# LaserCutterControlSimple.net
KiCad netlist of a schematic drawn in EAGLE
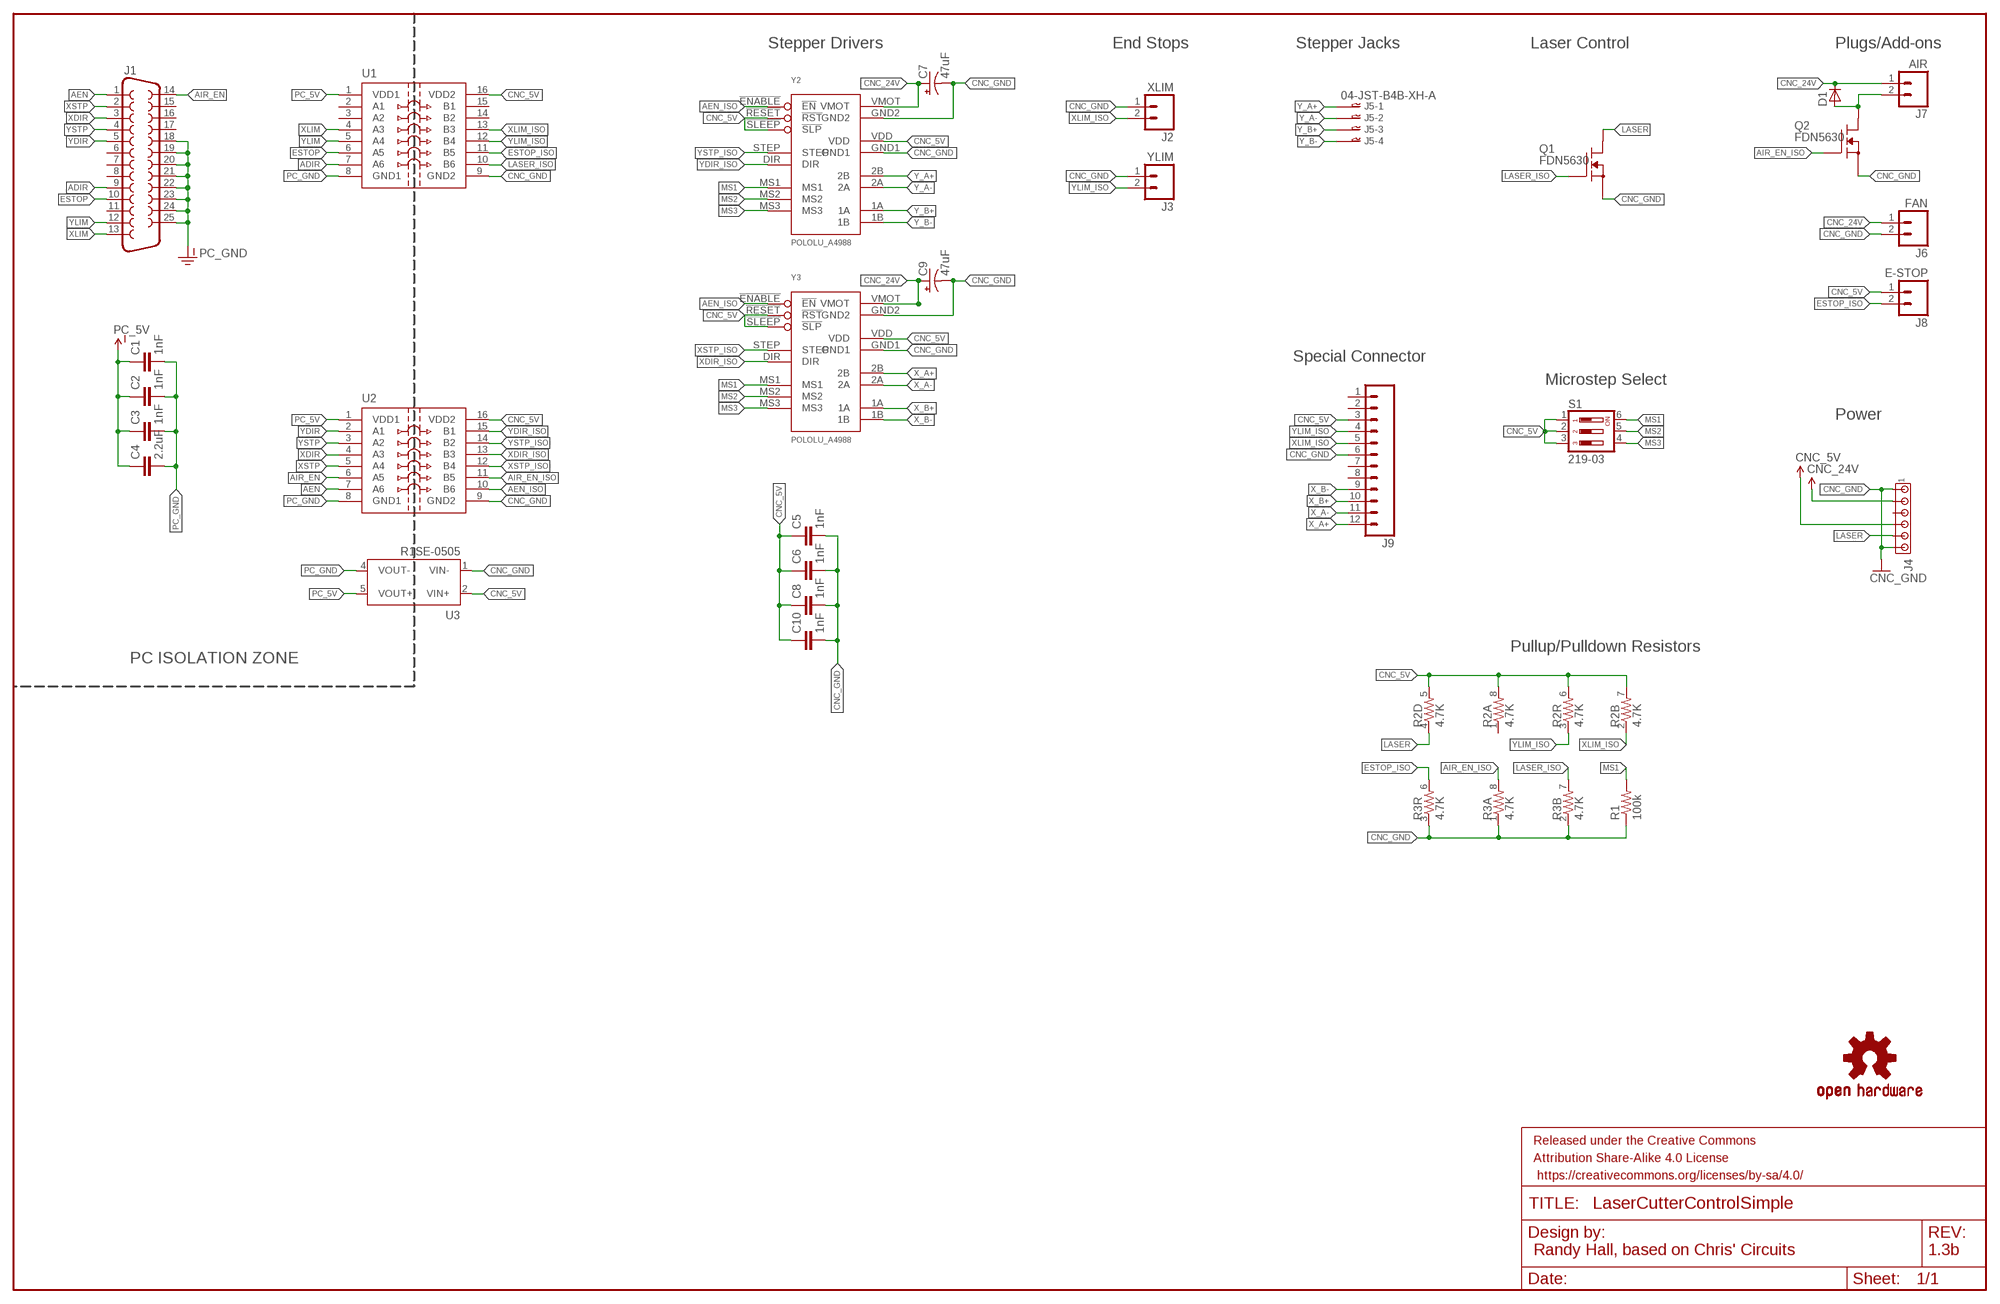
[diagram p0: schematic, sheet 1]

(export (version "E")
  (design (tool "Eeschema 10.0.6"))
  (components
    (comp (ref "C1")
      (value "1nF")
      (footprint "eagle-import:0603-CAP")
      (libsource (lib "eagle-import") (part "1NF/1000PF-50V-10%(0603)"))
    )
    (comp (ref "C2")
      (value "1nF")
      (footprint "eagle-import:0603-CAP")
      (libsource (lib "eagle-import") (part "1NF/1000PF-50V-10%(0603)"))
    )
    (comp (ref "C3")
      (value "1nF")
      (footprint "eagle-import:0603-CAP")
      (libsource (lib "eagle-import") (part "1NF/1000PF-50V-10%(0603)"))
    )
    (comp (ref "C4")
      (value "2.2uF")
      (footprint "eagle-import:0603-CAP")
      (libsource (lib "eagle-import") (part "1NF/1000PF-50V-10%(0603)"))
    )
    (comp (ref "C5")
      (value "1nF")
      (footprint "eagle-import:0603-CAP")
      (libsource (lib "eagle-import") (part "1NF/1000PF-50V-10%(0603)"))
    )
    (comp (ref "C6")
      (value "1nF")
      (footprint "eagle-import:0603-CAP")
      (libsource (lib "eagle-import") (part "1NF/1000PF-50V-10%(0603)"))
    )
    (comp (ref "C7")
      (value "47uF")
      (footprint "eagle-import:PANASONIC_E")
      (libsource (lib "eagle-import") (part "CPOL-USE"))
    )
    (comp (ref "C8")
      (value "1nF")
      (footprint "eagle-import:0603-CAP")
      (libsource (lib "eagle-import") (part "1NF/1000PF-50V-10%(0603)"))
    )
    (comp (ref "C9")
      (value "47uF")
      (footprint "eagle-import:PANASONIC_E")
      (libsource (lib "eagle-import") (part "CPOL-USE"))
    )
    (comp (ref "C10")
      (value "1nF")
      (footprint "eagle-import:0603-CAP")
      (libsource (lib "eagle-import") (part "1NF/1000PF-50V-10%(0603)"))
    )
    (comp (ref "D1")
      (value "D-SOD123")
      (footprint "eagle-import:SOD123")
      (libsource (lib "eagle-import") (part "D-SOD123"))
    )
    (comp (ref "FRAME1")
      (value "FRAME-LEDGER")
      (footprint "eagle-import:CREATIVE_COMMONS")
      (libsource (lib "eagle-import") (part "FRAME-LEDGER"))
    )
    (comp (ref "J1")
      (value "F25HP")
      (footprint "eagle-import:F25HP")
      (libsource (lib "eagle-import") (part "F25HP"))
    )
    (comp (ref "J2")
      (value "XLIM")
      (footprint "eagle-import:1X02")
      (libsource (lib "eagle-import") (part "M02PTH"))
    )
    (comp (ref "J3")
      (value "YLIM")
      (footprint "eagle-import:1X02")
      (libsource (lib "eagle-import") (part "M02PTH"))
    )
    (comp (ref "J4")
      (value "MTA06-156")
      (footprint "eagle-import:1X6MTA")
      (libsource (lib "eagle-import") (part "MTA06-156"))
    )
    (comp (ref "J5")
      (value "04-JST-B4B-XH-A")
      (footprint "eagle-import:B4B-XH")
      (libsource (lib "eagle-import") (part "04-JST-B4B-XH-A"))
    )
    (comp (ref "J6")
      (value "FAN")
      (footprint "eagle-import:1X02")
      (libsource (lib "eagle-import") (part "M02PTH"))
    )
    (comp (ref "J7")
      (value "AIR")
      (footprint "eagle-import:1X02")
      (libsource (lib "eagle-import") (part "M02PTH"))
    )
    (comp (ref "J8")
      (value "E-STOP")
      (footprint "eagle-import:1X02")
      (libsource (lib "eagle-import") (part "M02PTH"))
    )
    (comp (ref "J9")
      (value "M12")
      (footprint "eagle-import:12P")
      (libsource (lib "eagle-import") (part "M12"))
    )
    (comp (ref "LOGO1")
      (value "OSHW-LOGOM")
      (footprint "eagle-import:OSHW-LOGO-M")
      (libsource (lib "eagle-import") (part "OSHW-LOGOM"))
    )
    (comp (ref "Q1")
      (value "FDN5630")
      (footprint "eagle-import:SOT23")
      (libsource (lib "eagle-import") (part "FDN5630"))
    )
    (comp (ref "Q2")
      (value "FDN5630")
      (footprint "eagle-import:SOT23")
      (libsource (lib "eagle-import") (part "FDN5630"))
    )
    (comp (ref "R1")
      (value "100k")
      (footprint "eagle-import:0603-RES")
      (libsource (lib "eagle-import") (part "100KOHM1/10W1%(0603)"))
    )
    (comp (ref "R2")
      (value "4.7K")
      (footprint "eagle-import:0603-ARV")
      (libsource (lib "eagle-import") (part "RESISTOR-ARRAY0603-ARV"))
    )
    (comp (ref "R3")
      (value "4.7K")
      (footprint "eagle-import:0603-ARV")
      (libsource (lib "eagle-import") (part "RESISTOR-ARRAY0603-ARV"))
    )
    (comp (ref "S1")
      (value "219-03")
      (footprint "eagle-import:CTS-219-03")
      (libsource (lib "eagle-import") (part "219-03"))
    )
    (comp (ref "U1")
      (value "SI8460IS1")
      (footprint "eagle-import:SO16")
      (libsource (lib "eagle-import") (part "SI8460IS1"))
    )
    (comp (ref "U2")
      (value "SI8460IS1")
      (footprint "eagle-import:SO16")
      (libsource (lib "eagle-import") (part "SI8460IS1"))
    )
    (comp (ref "U3")
      (value "R1SE-0505")
      (footprint "eagle-import:SMD5")
      (libsource (lib "eagle-import") (part "R1SE-0505"))
    )
    (comp (ref "Y2")
      (value "POLOLU_A4988")
      (footprint "eagle-import:POLOLU_STEPPER_DRIVER")
      (libsource (lib "eagle-import") (part "POLOLU_A4988"))
    )
    (comp (ref "Y3")
      (value "POLOLU_A4988")
      (footprint "eagle-import:POLOLU_STEPPER_DRIVER")
      (libsource (lib "eagle-import") (part "POLOLU_A4988"))
    )
  )
  (nets
    (net (code "1") (name "ADIR") (class "Default")
      (node (ref "J1") (pin "9") (pinfunction "9_9") (pintype "passive"))
      (node (ref "U1") (pin "7") (pinfunction "A6_7") (pintype "input"))
    )
    (net (code "2") (name "AEN") (class "Default")
      (node (ref "J1") (pin "1") (pinfunction "1_1") (pintype "passive"))
      (node (ref "U2") (pin "7") (pinfunction "A6_7") (pintype "input"))
    )
    (net (code "3") (name "AEN_ISO") (class "Default")
      (node (ref "U2") (pin "10") (pinfunction "B6_10") (pintype "output"))
      (node (ref "Y2") (pin "!ENABLE") (pinfunction "~{EN}_!ENABLE") (pintype "input"))
      (node (ref "Y3") (pin "!ENABLE") (pinfunction "~{EN}_!ENABLE") (pintype "input"))
    )
    (net (code "4") (name "AIR_EN") (class "Default")
      (node (ref "J1") (pin "14") (pinfunction "14_14") (pintype "passive"))
      (node (ref "U2") (pin "6") (pinfunction "A5_6") (pintype "input"))
    )
    (net (code "5") (name "AIR_EN_ISO") (class "Default")
      (node (ref "Q2") (pin "1") (pinfunction "G_1") (pintype "passive"))
      (node (ref "R3") (pin "8") (pinfunction "2_8") (pintype "passive"))
      (node (ref "U2") (pin "11") (pinfunction "B5_11") (pintype "output"))
    )
    (net (code "6") (name "CNC_5V") (class "Default")
      (node (ref "C10") (pin "1") (pinfunction "1_1") (pintype "passive"))
      (node (ref "C5") (pin "1") (pinfunction "1_1") (pintype "passive"))
      (node (ref "C6") (pin "1") (pinfunction "1_1") (pintype "passive"))
      (node (ref "C8") (pin "1") (pinfunction "1_1") (pintype "passive"))
      (node (ref "J4") (pin "4") (pinfunction "4_4") (pintype "passive"))
      (node (ref "J8") (pin "1") (pinfunction "1_1") (pintype "passive"))
      (node (ref "J9") (pin "3") (pinfunction "3_3") (pintype "passive"))
      (node (ref "R2") (pin "5") (pinfunction "2_5") (pintype "passive"))
      (node (ref "R2") (pin "6") (pinfunction "2_6") (pintype "passive"))
      (node (ref "R2") (pin "7") (pinfunction "2_7") (pintype "passive"))
      (node (ref "R2") (pin "8") (pinfunction "2_8") (pintype "passive"))
      (node (ref "S1") (pin "1") (pinfunction "1_1") (pintype "passive"))
      (node (ref "S1") (pin "2") (pinfunction "2_2") (pintype "passive"))
      (node (ref "S1") (pin "3") (pinfunction "3_3") (pintype "passive"))
      (node (ref "U1") (pin "16") (pinfunction "VDD2_16") (pintype "power_in"))
      (node (ref "U2") (pin "16") (pinfunction "VDD2_16") (pintype "power_in"))
      (node (ref "U3") (pin "2") (pinfunction "VIN+_2") (pintype "input"))
      (node (ref "Y2") (pin "!RESET") (pinfunction "~{RST}_!RESET") (pintype "input"))
      (node (ref "Y2") (pin "!SLEEP") (pinfunction "~{SLP}_!SLEEP") (pintype "input"))
      (node (ref "Y2") (pin "VDD") (pinfunction "VDD_VDD") (pintype "power_in"))
      (node (ref "Y3") (pin "!RESET") (pinfunction "~{RST}_!RESET") (pintype "input"))
      (node (ref "Y3") (pin "!SLEEP") (pinfunction "~{SLP}_!SLEEP") (pintype "input"))
      (node (ref "Y3") (pin "VDD") (pinfunction "VDD_VDD") (pintype "power_in"))
    )
    (net (code "7") (name "CNC_24V") (class "Default")
      (node (ref "C7") (pin "+") (pinfunction "+_+") (pintype "passive"))
      (node (ref "C9") (pin "+") (pinfunction "+_+") (pintype "passive"))
      (node (ref "D1") (pin "1") (pinfunction "C_1") (pintype "passive"))
      (node (ref "J4") (pin "2") (pinfunction "2_2") (pintype "passive"))
      (node (ref "J6") (pin "1") (pinfunction "1_1") (pintype "passive"))
      (node (ref "J7") (pin "1") (pinfunction "1_1") (pintype "passive"))
      (node (ref "Y2") (pin "VMOT") (pinfunction "VMOT_VMOT") (pintype "power_in"))
      (node (ref "Y3") (pin "VMOT") (pinfunction "VMOT_VMOT") (pintype "power_in"))
    )
    (net (code "8") (name "CNC_GND") (class "Default")
      (node (ref "C10") (pin "2") (pinfunction "2_2") (pintype "passive"))
      (node (ref "C5") (pin "2") (pinfunction "2_2") (pintype "passive"))
      (node (ref "C6") (pin "2") (pinfunction "2_2") (pintype "passive"))
      (node (ref "C7") (pin "-") (pinfunction "-_-") (pintype "passive"))
      (node (ref "C8") (pin "2") (pinfunction "2_2") (pintype "passive"))
      (node (ref "C9") (pin "-") (pinfunction "-_-") (pintype "passive"))
      (node (ref "J2") (pin "1") (pinfunction "1_1") (pintype "passive"))
      (node (ref "J3") (pin "1") (pinfunction "1_1") (pintype "passive"))
      (node (ref "J4") (pin "1") (pinfunction "1_1") (pintype "passive"))
      (node (ref "J4") (pin "6") (pinfunction "6_6") (pintype "passive"))
      (node (ref "J6") (pin "2") (pinfunction "2_2") (pintype "passive"))
      (node (ref "J9") (pin "6") (pinfunction "6_6") (pintype "passive"))
      (node (ref "Q1") (pin "2") (pinfunction "S_2") (pintype "passive"))
      (node (ref "Q2") (pin "2") (pinfunction "S_2") (pintype "passive"))
      (node (ref "R1") (pin "1") (pinfunction "1_1") (pintype "passive"))
      (node (ref "R3") (pin "1") (pinfunction "1_1") (pintype "passive"))
      (node (ref "R3") (pin "2") (pinfunction "1_2") (pintype "passive"))
      (node (ref "R3") (pin "3") (pinfunction "1_3") (pintype "passive"))
      (node (ref "U1") (pin "9") (pinfunction "GND2_9") (pintype "power_in"))
      (node (ref "U2") (pin "9") (pinfunction "GND2_9") (pintype "power_in"))
      (node (ref "U3") (pin "1") (pinfunction "VIN-_1") (pintype "power_in"))
      (node (ref "Y2") (pin "GND1") (pinfunction "GND1_GND1") (pintype "power_in"))
      (node (ref "Y2") (pin "GND2") (pinfunction "GND2_GND2") (pintype "power_in"))
      (node (ref "Y3") (pin "GND1") (pinfunction "GND1_GND1") (pintype "power_in"))
      (node (ref "Y3") (pin "GND2") (pinfunction "GND2_GND2") (pintype "power_in"))
    )
    (net (code "9") (name "ESTOP") (class "Default")
      (node (ref "J1") (pin "10") (pinfunction "10_10") (pintype "passive"))
      (node (ref "U1") (pin "6") (pinfunction "A5_6") (pintype "input"))
    )
    (net (code "10") (name "ESTOP_ISO") (class "Default")
      (node (ref "J8") (pin "2") (pinfunction "2_2") (pintype "passive"))
      (node (ref "R3") (pin "6") (pinfunction "2_6") (pintype "passive"))
      (node (ref "U1") (pin "11") (pinfunction "B5_11") (pintype "output"))
    )
    (net (code "11") (name "LASER") (class "Default")
      (node (ref "J4") (pin "5") (pinfunction "5_5") (pintype "passive"))
      (node (ref "Q1") (pin "3") (pinfunction "D_3") (pintype "passive"))
      (node (ref "R2") (pin "4") (pinfunction "1_4") (pintype "passive"))
    )
    (net (code "12") (name "LASER_ISO") (class "Default")
      (node (ref "Q1") (pin "1") (pinfunction "G_1") (pintype "passive"))
      (node (ref "R3") (pin "7") (pinfunction "2_7") (pintype "passive"))
      (node (ref "U1") (pin "10") (pinfunction "B6_10") (pintype "output"))
    )
    (net (code "13") (name "MS1") (class "Default")
      (node (ref "R1") (pin "2") (pinfunction "2_2") (pintype "passive"))
      (node (ref "S1") (pin "6") (pinfunction "6_6") (pintype "passive"))
      (node (ref "Y2") (pin "MS1") (pinfunction "MS1_MS1") (pintype "input"))
      (node (ref "Y3") (pin "MS1") (pinfunction "MS1_MS1") (pintype "input"))
    )
    (net (code "14") (name "MS2") (class "Default")
      (node (ref "S1") (pin "5") (pinfunction "5_5") (pintype "passive"))
      (node (ref "Y2") (pin "MS2") (pinfunction "MS2_MS2") (pintype "input"))
      (node (ref "Y3") (pin "MS2") (pinfunction "MS2_MS2") (pintype "input"))
    )
    (net (code "15") (name "MS3") (class "Default")
      (node (ref "S1") (pin "4") (pinfunction "4_4") (pintype "passive"))
      (node (ref "Y2") (pin "MS3") (pinfunction "MS3_MS3") (pintype "input"))
      (node (ref "Y3") (pin "MS3") (pinfunction "MS3_MS3") (pintype "input"))
    )
    (net (code "16") (name "Net-(D1-A)") (class "Default")
      (node (ref "D1") (pin "2") (pinfunction "A_2") (pintype "passive"))
      (node (ref "J7") (pin "2") (pinfunction "2_2") (pintype "passive"))
      (node (ref "Q2") (pin "3") (pinfunction "D_3") (pintype "passive"))
    )
    (net (code "17") (name "PC_5V") (class "Default")
      (node (ref "C1") (pin "1") (pinfunction "1_1") (pintype "passive"))
      (node (ref "C2") (pin "1") (pinfunction "1_1") (pintype "passive"))
      (node (ref "C3") (pin "1") (pinfunction "1_1") (pintype "passive"))
      (node (ref "C4") (pin "1") (pinfunction "1_1") (pintype "passive"))
      (node (ref "U1") (pin "1") (pinfunction "VDD1_1") (pintype "power_in"))
      (node (ref "U2") (pin "1") (pinfunction "VDD1_1") (pintype "power_in"))
      (node (ref "U3") (pin "5") (pinfunction "VOUT+_5") (pintype "output"))
    )
    (net (code "18") (name "PC_GND") (class "Default")
      (node (ref "C1") (pin "2") (pinfunction "2_2") (pintype "passive"))
      (node (ref "C2") (pin "2") (pinfunction "2_2") (pintype "passive"))
      (node (ref "C3") (pin "2") (pinfunction "2_2") (pintype "passive"))
      (node (ref "C4") (pin "2") (pinfunction "2_2") (pintype "passive"))
      (node (ref "J1") (pin "18") (pinfunction "18_18") (pintype "passive"))
      (node (ref "J1") (pin "19") (pinfunction "19_19") (pintype "passive"))
      (node (ref "J1") (pin "20") (pinfunction "20_20") (pintype "passive"))
      (node (ref "J1") (pin "21") (pinfunction "21_21") (pintype "passive"))
      (node (ref "J1") (pin "22") (pinfunction "22_22") (pintype "passive"))
      (node (ref "J1") (pin "23") (pinfunction "23_23") (pintype "passive"))
      (node (ref "J1") (pin "24") (pinfunction "24_24") (pintype "passive"))
      (node (ref "J1") (pin "25") (pinfunction "25_25") (pintype "passive"))
      (node (ref "U1") (pin "8") (pinfunction "GND1_8") (pintype "power_in"))
      (node (ref "U2") (pin "8") (pinfunction "GND1_8") (pintype "power_in"))
      (node (ref "U3") (pin "4") (pinfunction "VOUT-_4") (pintype "output"))
    )
    (net (code "19") (name "XDIR") (class "Default")
      (node (ref "J1") (pin "3") (pinfunction "3_3") (pintype "passive"))
      (node (ref "U2") (pin "4") (pinfunction "A3_4") (pintype "input"))
    )
    (net (code "20") (name "XDIR_ISO") (class "Default")
      (node (ref "U2") (pin "13") (pinfunction "B3_13") (pintype "output"))
      (node (ref "Y3") (pin "DIR") (pinfunction "DIR_DIR") (pintype "input"))
    )
    (net (code "21") (name "XLIM") (class "Default")
      (node (ref "J1") (pin "13") (pinfunction "13_13") (pintype "passive"))
      (node (ref "U1") (pin "4") (pinfunction "A3_4") (pintype "input"))
    )
    (net (code "22") (name "XLIM_ISO") (class "Default")
      (node (ref "J2") (pin "2") (pinfunction "2_2") (pintype "passive"))
      (node (ref "J9") (pin "5") (pinfunction "5_5") (pintype "passive"))
      (node (ref "R2") (pin "2") (pinfunction "1_2") (pintype "passive"))
      (node (ref "U1") (pin "13") (pinfunction "B3_13") (pintype "output"))
    )
    (net (code "23") (name "XSTP") (class "Default")
      (node (ref "J1") (pin "2") (pinfunction "2_2") (pintype "passive"))
      (node (ref "U2") (pin "5") (pinfunction "A4_5") (pintype "input"))
    )
    (net (code "24") (name "XSTP_ISO") (class "Default")
      (node (ref "U2") (pin "12") (pinfunction "B4_12") (pintype "output"))
      (node (ref "Y3") (pin "STEP") (pinfunction "STEP_STEP") (pintype "input"))
    )
    (net (code "25") (name "X_A+") (class "Default")
      (node (ref "J9") (pin "12") (pinfunction "12_12") (pintype "passive"))
      (node (ref "Y3") (pin "2B") (pinfunction "2B_2B") (pintype "output"))
    )
    (net (code "26") (name "X_A-") (class "Default")
      (node (ref "J9") (pin "11") (pinfunction "11_11") (pintype "passive"))
      (node (ref "Y3") (pin "2A") (pinfunction "2A_2A") (pintype "output"))
    )
    (net (code "27") (name "X_B+") (class "Default")
      (node (ref "J9") (pin "10") (pinfunction "10_10") (pintype "passive"))
      (node (ref "Y3") (pin "1A") (pinfunction "1A_1A") (pintype "output"))
    )
    (net (code "28") (name "X_B-") (class "Default")
      (node (ref "J9") (pin "9") (pinfunction "9_9") (pintype "passive"))
      (node (ref "Y3") (pin "1B") (pinfunction "1B_1B") (pintype "output"))
    )
    (net (code "29") (name "YDIR") (class "Default")
      (node (ref "J1") (pin "5") (pinfunction "5_5") (pintype "passive"))
      (node (ref "U2") (pin "2") (pinfunction "A1_2") (pintype "input"))
    )
    (net (code "30") (name "YDIR_ISO") (class "Default")
      (node (ref "U2") (pin "15") (pinfunction "B1_15") (pintype "output"))
      (node (ref "Y2") (pin "DIR") (pinfunction "DIR_DIR") (pintype "input"))
    )
    (net (code "31") (name "YLIM") (class "Default")
      (node (ref "J1") (pin "12") (pinfunction "12_12") (pintype "passive"))
      (node (ref "U1") (pin "5") (pinfunction "A4_5") (pintype "input"))
    )
    (net (code "32") (name "YLIM_ISO") (class "Default")
      (node (ref "J3") (pin "2") (pinfunction "2_2") (pintype "passive"))
      (node (ref "J9") (pin "4") (pinfunction "4_4") (pintype "passive"))
      (node (ref "R2") (pin "3") (pinfunction "1_3") (pintype "passive"))
      (node (ref "U1") (pin "12") (pinfunction "B4_12") (pintype "output"))
    )
    (net (code "33") (name "YSTP") (class "Default")
      (node (ref "J1") (pin "4") (pinfunction "4_4") (pintype "passive"))
      (node (ref "U2") (pin "3") (pinfunction "A2_3") (pintype "input"))
    )
    (net (code "34") (name "YSTP_ISO") (class "Default")
      (node (ref "U2") (pin "14") (pinfunction "B2_14") (pintype "output"))
      (node (ref "Y2") (pin "STEP") (pinfunction "STEP_STEP") (pintype "input"))
    )
    (net (code "35") (name "Y_A+") (class "Default")
      (node (ref "J5") (pin "P$1") (pinfunction "1_P$1") (pintype "passive"))
      (node (ref "Y2") (pin "2B") (pinfunction "2B_2B") (pintype "output"))
    )
    (net (code "36") (name "Y_A-") (class "Default")
      (node (ref "J5") (pin "P$2") (pinfunction "1_P$2") (pintype "passive"))
      (node (ref "Y2") (pin "2A") (pinfunction "2A_2A") (pintype "output"))
    )
    (net (code "37") (name "Y_B+") (class "Default")
      (node (ref "J5") (pin "P$3") (pinfunction "1_P$3") (pintype "passive"))
      (node (ref "Y2") (pin "1A") (pinfunction "1A_1A") (pintype "output"))
    )
    (net (code "38") (name "Y_B-") (class "Default")
      (node (ref "J5") (pin "P$4") (pinfunction "1_P$4") (pintype "passive"))
      (node (ref "Y2") (pin "1B") (pinfunction "1B_1B") (pintype "output"))
    )
    (net (code "39") (name "unconnected-(J1-Pad6)") (class "Default")
      (node (ref "J1") (pin "6") (pinfunction "6_6") (pintype "passive"))
    )
    (net (code "40") (name "unconnected-(J1-Pad7)") (class "Default")
      (node (ref "J1") (pin "7") (pinfunction "7_7") (pintype "passive"))
    )
    (net (code "41") (name "unconnected-(J1-Pad8)") (class "Default")
      (node (ref "J1") (pin "8") (pinfunction "8_8") (pintype "passive"))
    )
    (net (code "42") (name "unconnected-(J1-Pad11)") (class "Default")
      (node (ref "J1") (pin "11") (pinfunction "11_11") (pintype "passive"))
    )
    (net (code "43") (name "unconnected-(J1-Pad15)") (class "Default")
      (node (ref "J1") (pin "15") (pinfunction "15_15") (pintype "passive"))
    )
    (net (code "44") (name "unconnected-(J1-Pad16)") (class "Default")
      (node (ref "J1") (pin "16") (pinfunction "16_16") (pintype "passive"))
    )
    (net (code "45") (name "unconnected-(J1-Pad17)") (class "Default")
      (node (ref "J1") (pin "17") (pinfunction "17_17") (pintype "passive"))
    )
    (net (code "46") (name "unconnected-(J4-Pad3)") (class "Default")
      (node (ref "J4") (pin "3") (pinfunction "3_3") (pintype "passive"))
    )
    (net (code "47") (name "unconnected-(J9-Pad1)") (class "Default")
      (node (ref "J9") (pin "1") (pinfunction "1_1") (pintype "passive"))
    )
    (net (code "48") (name "unconnected-(J9-Pad2)") (class "Default")
      (node (ref "J9") (pin "2") (pinfunction "2_2") (pintype "passive"))
    )
    (net (code "49") (name "unconnected-(J9-Pad7)") (class "Default")
      (node (ref "J9") (pin "7") (pinfunction "7_7") (pintype "passive"))
    )
    (net (code "50") (name "unconnected-(J9-Pad8)") (class "Default")
      (node (ref "J9") (pin "8") (pinfunction "8_8") (pintype "passive"))
    )
    (net (code "51") (name "unconnected-(R2-Pad1)") (class "Default")
      (node (ref "R2") (pin "1") (pinfunction "1_1") (pintype "passive"))
    )
    (net (code "52") (name "unconnected-(U1-A1-Pad2)") (class "Default")
      (node (ref "U1") (pin "2") (pinfunction "A1_2") (pintype "input"))
    )
    (net (code "53") (name "unconnected-(U1-A2-Pad3)") (class "Default")
      (node (ref "U1") (pin "3") (pinfunction "A2_3") (pintype "input"))
    )
    (net (code "54") (name "unconnected-(U1-B1-Pad15)") (class "Default")
      (node (ref "U1") (pin "15") (pinfunction "B1_15") (pintype "output"))
    )
    (net (code "55") (name "unconnected-(U1-B2-Pad14)") (class "Default")
      (node (ref "U1") (pin "14") (pinfunction "B2_14") (pintype "output"))
    )
  )
)
